# ATX_PSU_rev0_1.net
KiCad netlist of a schematic drawn in EAGLE
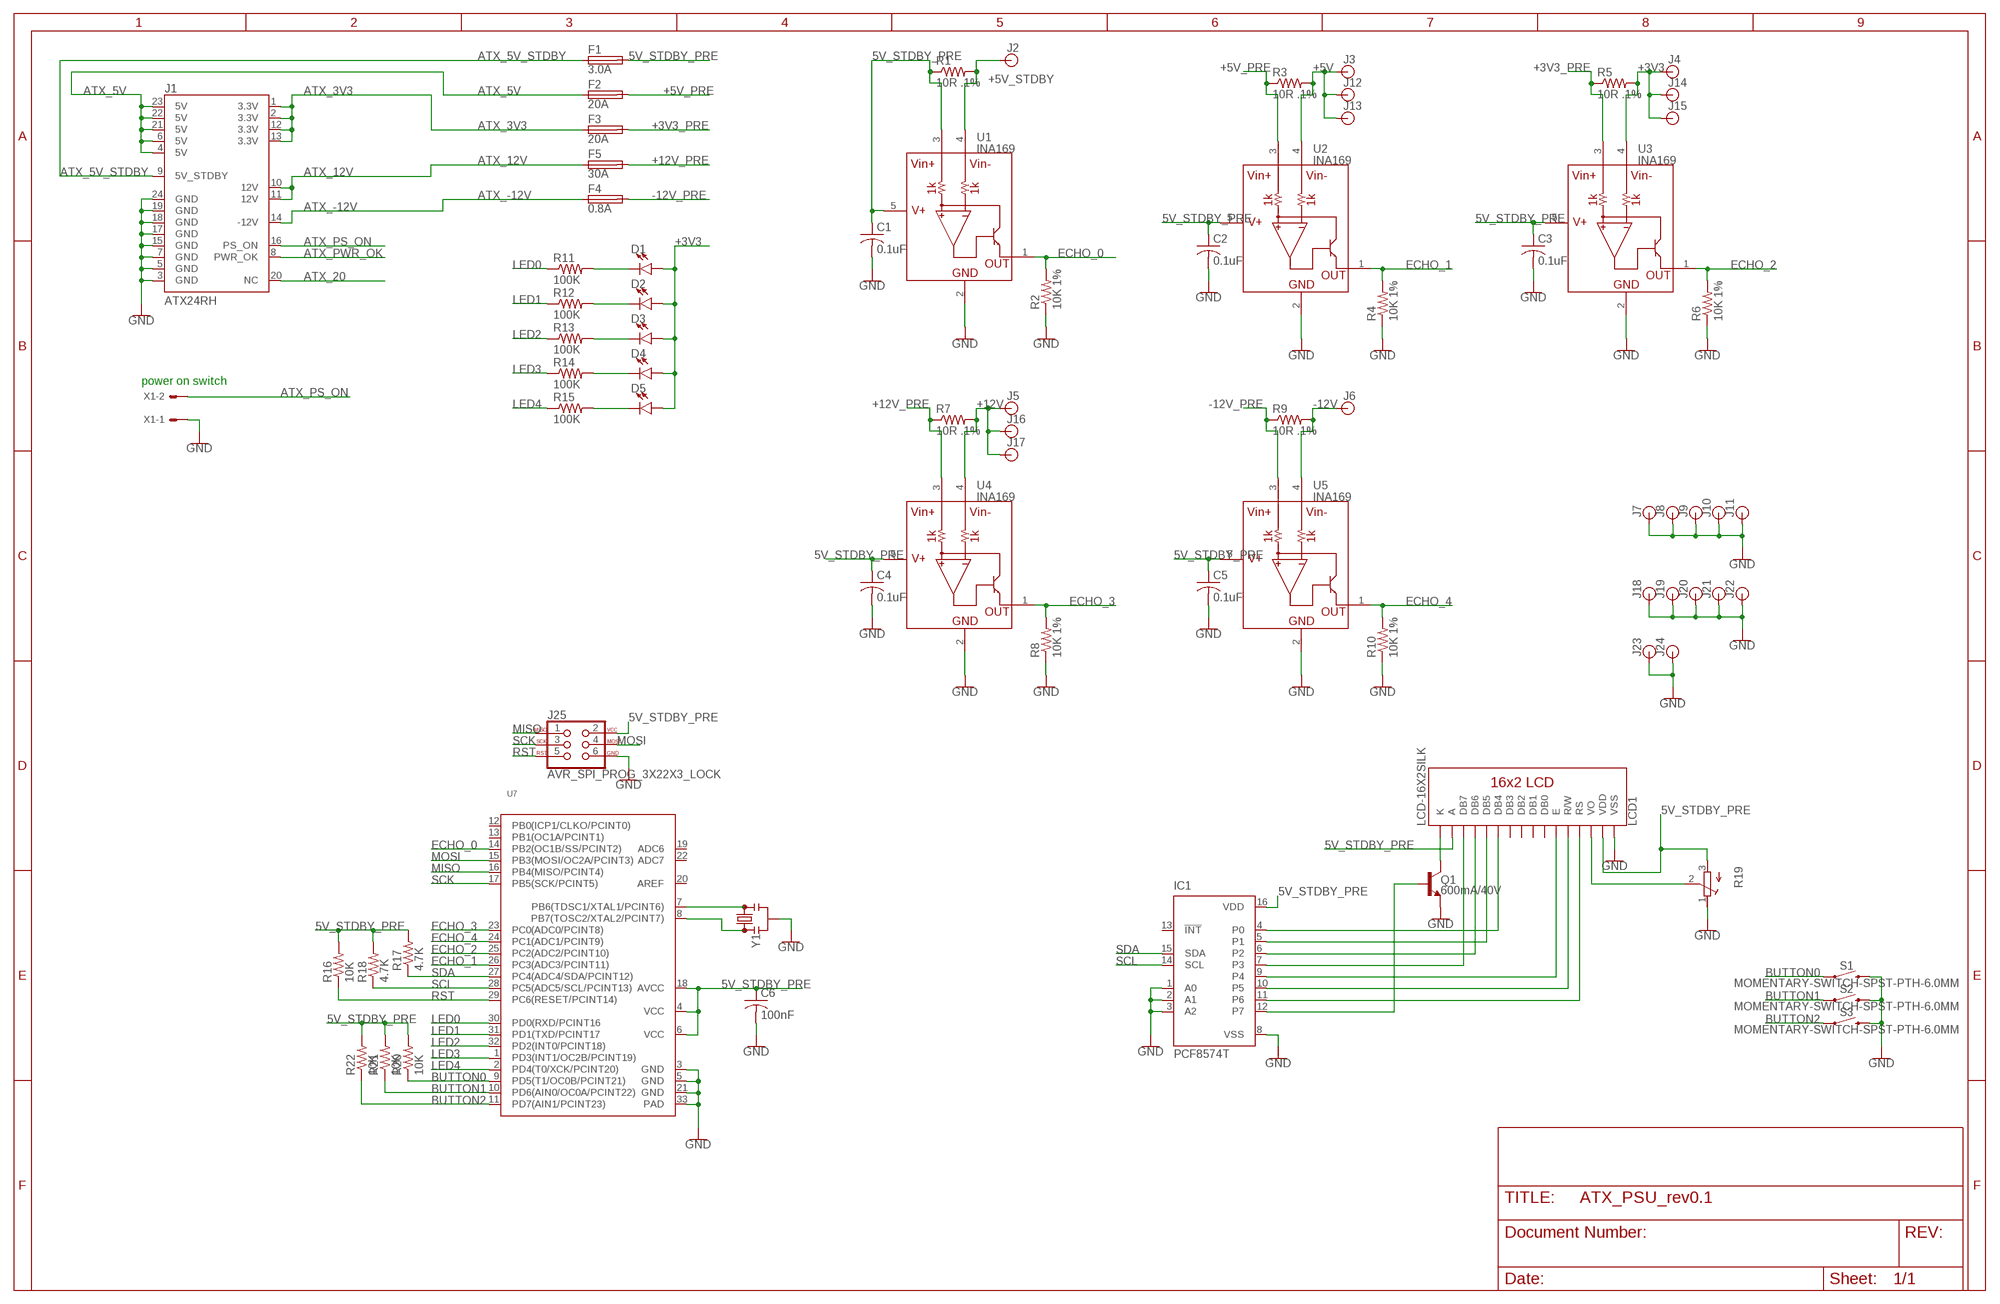
[diagram p0: schematic, sheet 1]

(export (version "E")
  (design (tool "Eeschema 10.0.6"))
  (components
    (comp (ref "C1")
      (value "0.1uF")
      (footprint "eagle-import:C1206")
      (libsource (lib "eagle-import") (part "C-USC1206"))
    )
    (comp (ref "C2")
      (value "0.1uF")
      (footprint "eagle-import:C1206")
      (libsource (lib "eagle-import") (part "C-USC1206"))
    )
    (comp (ref "C3")
      (value "0.1uF")
      (footprint "eagle-import:C1206")
      (libsource (lib "eagle-import") (part "C-USC1206"))
    )
    (comp (ref "C4")
      (value "0.1uF")
      (footprint "eagle-import:C1206")
      (libsource (lib "eagle-import") (part "C-USC1206"))
    )
    (comp (ref "C5")
      (value "0.1uF")
      (footprint "eagle-import:C1206")
      (libsource (lib "eagle-import") (part "C-USC1206"))
    )
    (comp (ref "C6")
      (value "100nF")
      (footprint "eagle-import:C1206")
      (libsource (lib "eagle-import") (part "C-USC1206"))
    )
    (comp (ref "D1")
      (value "LED-FKIT-1206")
      (footprint "eagle-import:FKIT-LED-1206")
      (libsource (lib "eagle-import") (part "LED-FKIT-1206"))
    )
    (comp (ref "D2")
      (value "LED-FKIT-1206")
      (footprint "eagle-import:FKIT-LED-1206")
      (libsource (lib "eagle-import") (part "LED-FKIT-1206"))
    )
    (comp (ref "D3")
      (value "LED-FKIT-1206")
      (footprint "eagle-import:FKIT-LED-1206")
      (libsource (lib "eagle-import") (part "LED-FKIT-1206"))
    )
    (comp (ref "D4")
      (value "LED-FKIT-1206")
      (footprint "eagle-import:FKIT-LED-1206")
      (libsource (lib "eagle-import") (part "LED-FKIT-1206"))
    )
    (comp (ref "D5")
      (value "LED-FKIT-1206")
      (footprint "eagle-import:FKIT-LED-1206")
      (libsource (lib "eagle-import") (part "LED-FKIT-1206"))
    )
    (comp (ref "F1")
      (value "3.0A")
      (footprint "eagle-import:FUSE_HOLDER_5X20MM")
      (libsource (lib "eagle-import") (part "FUSEBLANK_5X20MM"))
    )
    (comp (ref "F2")
      (value "20A")
      (footprint "eagle-import:FUSE_HOLDER_5X20MM")
      (libsource (lib "eagle-import") (part "FUSEBLANK_5X20MM"))
    )
    (comp (ref "F3")
      (value "20A")
      (footprint "eagle-import:FUSE_HOLDER_5X20MM")
      (libsource (lib "eagle-import") (part "FUSEBLANK_5X20MM"))
    )
    (comp (ref "F4")
      (value "0.8A")
      (footprint "eagle-import:FUSE_HOLDER_5X20MM")
      (libsource (lib "eagle-import") (part "FUSEBLANK_5X20MM"))
    )
    (comp (ref "F5")
      (value "30A")
      (footprint "eagle-import:FUSE_HOLDER_5X20MM")
      (libsource (lib "eagle-import") (part "FUSEBLANK_5X20MM"))
    )
    (comp (ref "IC1")
      (value "PCF8574T")
      (footprint "eagle-import:SO16W")
      (fields (field (name "MPN") "PCF8574T/3,512"))
      (libsource (lib "eagle-import") (part "PCF8574T"))
    )
    (comp (ref "J1")
      (value "ATX24RH")
      (footprint "eagle-import:ATX24_RIGHT_ANGLE")
      (libsource (lib "eagle-import") (part "ATX24RH"))
    )
    (comp (ref "J2")
      (value "BANANA_CONN")
      (footprint "eagle-import:BANANA_CONN")
      (libsource (lib "eagle-import") (part "BANANA_CONN"))
    )
    (comp (ref "J3")
      (value "BANANA_CONN")
      (footprint "eagle-import:BANANA_CONN")
      (libsource (lib "eagle-import") (part "BANANA_CONN"))
    )
    (comp (ref "J4")
      (value "BANANA_CONN")
      (footprint "eagle-import:BANANA_CONN")
      (libsource (lib "eagle-import") (part "BANANA_CONN"))
    )
    (comp (ref "J5")
      (value "BANANA_CONN")
      (footprint "eagle-import:BANANA_CONN")
      (libsource (lib "eagle-import") (part "BANANA_CONN"))
    )
    (comp (ref "J6")
      (value "BANANA_CONN")
      (footprint "eagle-import:BANANA_CONN")
      (libsource (lib "eagle-import") (part "BANANA_CONN"))
    )
    (comp (ref "J7")
      (value "BANANA_CONN")
      (footprint "eagle-import:BANANA_CONN")
      (libsource (lib "eagle-import") (part "BANANA_CONN"))
    )
    (comp (ref "J8")
      (value "BANANA_CONN")
      (footprint "eagle-import:BANANA_CONN")
      (libsource (lib "eagle-import") (part "BANANA_CONN"))
    )
    (comp (ref "J9")
      (value "BANANA_CONN")
      (footprint "eagle-import:BANANA_CONN")
      (libsource (lib "eagle-import") (part "BANANA_CONN"))
    )
    (comp (ref "J10")
      (value "BANANA_CONN")
      (footprint "eagle-import:BANANA_CONN")
      (libsource (lib "eagle-import") (part "BANANA_CONN"))
    )
    (comp (ref "J11")
      (value "BANANA_CONN")
      (footprint "eagle-import:BANANA_CONN")
      (libsource (lib "eagle-import") (part "BANANA_CONN"))
    )
    (comp (ref "J12")
      (value "BANANA_CONN")
      (footprint "eagle-import:BANANA_CONN")
      (libsource (lib "eagle-import") (part "BANANA_CONN"))
    )
    (comp (ref "J13")
      (value "BANANA_CONN")
      (footprint "eagle-import:BANANA_CONN")
      (libsource (lib "eagle-import") (part "BANANA_CONN"))
    )
    (comp (ref "J14")
      (value "BANANA_CONN")
      (footprint "eagle-import:BANANA_CONN")
      (libsource (lib "eagle-import") (part "BANANA_CONN"))
    )
    (comp (ref "J15")
      (value "BANANA_CONN")
      (footprint "eagle-import:BANANA_CONN")
      (libsource (lib "eagle-import") (part "BANANA_CONN"))
    )
    (comp (ref "J16")
      (value "BANANA_CONN")
      (footprint "eagle-import:BANANA_CONN")
      (libsource (lib "eagle-import") (part "BANANA_CONN"))
    )
    (comp (ref "J17")
      (value "BANANA_CONN")
      (footprint "eagle-import:BANANA_CONN")
      (libsource (lib "eagle-import") (part "BANANA_CONN"))
    )
    (comp (ref "J18")
      (value "BANANA_CONN")
      (footprint "eagle-import:BANANA_CONN")
      (libsource (lib "eagle-import") (part "BANANA_CONN"))
    )
    (comp (ref "J19")
      (value "BANANA_CONN")
      (footprint "eagle-import:BANANA_CONN")
      (libsource (lib "eagle-import") (part "BANANA_CONN"))
    )
    (comp (ref "J20")
      (value "BANANA_CONN")
      (footprint "eagle-import:BANANA_CONN")
      (libsource (lib "eagle-import") (part "BANANA_CONN"))
    )
    (comp (ref "J21")
      (value "BANANA_CONN")
      (footprint "eagle-import:BANANA_CONN")
      (libsource (lib "eagle-import") (part "BANANA_CONN"))
    )
    (comp (ref "J22")
      (value "BANANA_CONN")
      (footprint "eagle-import:BANANA_CONN")
      (libsource (lib "eagle-import") (part "BANANA_CONN"))
    )
    (comp (ref "J23")
      (value "BANANA_CONN")
      (footprint "eagle-import:BANANA_CONN")
      (libsource (lib "eagle-import") (part "BANANA_CONN"))
    )
    (comp (ref "J24")
      (value "BANANA_CONN")
      (footprint "eagle-import:BANANA_CONN")
      (libsource (lib "eagle-import") (part "BANANA_CONN"))
    )
    (comp (ref "J25")
      (value "AVR_SPI_PROG_3X22X3_LOCK")
      (footprint "eagle-import:2X3_LOCK")
      (libsource (lib "eagle-import") (part "AVR_SPI_PROG_3X22X3_LOCK"))
    )
    (comp (ref "LCD1")
      (value "LCD-16X2SILK")
      (footprint "eagle-import:LCD-16X2")
      (libsource (lib "eagle-import") (part "LCD-16X2SILK"))
    )
    (comp (ref "Q1")
      (value "600mA/40V")
      (footprint "eagle-import:SOT23-3")
      (libsource (lib "eagle-import") (part "TRANS_NPN-MMBT2222AL"))
    )
    (comp (ref "R1")
      (value "10R .1%")
      (footprint "eagle-import:R1206")
      (libsource (lib "eagle-import") (part "R-US_R1206"))
    )
    (comp (ref "R2")
      (value "10K 1%")
      (footprint "eagle-import:R1206")
      (libsource (lib "eagle-import") (part "R-US_R1206"))
    )
    (comp (ref "R3")
      (value "10R .1%")
      (footprint "eagle-import:R1206")
      (libsource (lib "eagle-import") (part "R-US_R1206"))
    )
    (comp (ref "R4")
      (value "10K 1%")
      (footprint "eagle-import:R1206")
      (libsource (lib "eagle-import") (part "R-US_R1206"))
    )
    (comp (ref "R5")
      (value "10R .1%")
      (footprint "eagle-import:R1206")
      (libsource (lib "eagle-import") (part "R-US_R1206"))
    )
    (comp (ref "R6")
      (value "10K 1%")
      (footprint "eagle-import:R1206")
      (libsource (lib "eagle-import") (part "R-US_R1206"))
    )
    (comp (ref "R7")
      (value "10R .1%")
      (footprint "eagle-import:R1206")
      (libsource (lib "eagle-import") (part "R-US_R1206"))
    )
    (comp (ref "R8")
      (value "10K 1%")
      (footprint "eagle-import:R1206")
      (libsource (lib "eagle-import") (part "R-US_R1206"))
    )
    (comp (ref "R9")
      (value "10R .1%")
      (footprint "eagle-import:R1206")
      (libsource (lib "eagle-import") (part "R-US_R1206"))
    )
    (comp (ref "R10")
      (value "10K 1%")
      (footprint "eagle-import:R1206")
      (libsource (lib "eagle-import") (part "R-US_R1206"))
    )
    (comp (ref "R11")
      (value "100K")
      (footprint "eagle-import:R1206")
      (libsource (lib "eagle-import") (part "R-US_R1206"))
    )
    (comp (ref "R12")
      (value "100K")
      (footprint "eagle-import:R1206")
      (libsource (lib "eagle-import") (part "R-US_R1206"))
    )
    (comp (ref "R13")
      (value "100K")
      (footprint "eagle-import:R1206")
      (libsource (lib "eagle-import") (part "R-US_R1206"))
    )
    (comp (ref "R14")
      (value "100K")
      (footprint "eagle-import:R1206")
      (libsource (lib "eagle-import") (part "R-US_R1206"))
    )
    (comp (ref "R15")
      (value "100K")
      (footprint "eagle-import:R1206")
      (libsource (lib "eagle-import") (part "R-US_R1206"))
    )
    (comp (ref "R16")
      (value "10K")
      (footprint "eagle-import:R1206")
      (libsource (lib "eagle-import") (part "R-US_R1206"))
    )
    (comp (ref "R17")
      (value "4.7K")
      (footprint "eagle-import:R1206")
      (libsource (lib "eagle-import") (part "R-US_R1206"))
    )
    (comp (ref "R18")
      (value "4.7K")
      (footprint "eagle-import:R1206")
      (libsource (lib "eagle-import") (part "R-US_R1206"))
    )
    (comp (ref "R19")
      (value "R-TRIMM3314G")
      (footprint "eagle-import:RTRIM3314G")
      (libsource (lib "eagle-import") (part "R-TRIMM3314G"))
    )
    (comp (ref "R20")
      (value "10K")
      (footprint "eagle-import:R1206")
      (libsource (lib "eagle-import") (part "R-US_R1206"))
    )
    (comp (ref "R21")
      (value "10K")
      (footprint "eagle-import:R1206")
      (libsource (lib "eagle-import") (part "R-US_R1206"))
    )
    (comp (ref "R22")
      (value "10K")
      (footprint "eagle-import:R1206")
      (libsource (lib "eagle-import") (part "R-US_R1206"))
    )
    (comp (ref "S1")
      (value "MOMENTARY-SWITCH-SPST-PTH-6.0MM")
      (footprint "eagle-import:TACTILE_SWITCH_PTH_6.0MM")
      (libsource (lib "eagle-import") (part "MOMENTARY-SWITCH-SPST-PTH-6.0MM"))
    )
    (comp (ref "S2")
      (value "MOMENTARY-SWITCH-SPST-PTH-6.0MM")
      (footprint "eagle-import:TACTILE_SWITCH_PTH_6.0MM")
      (libsource (lib "eagle-import") (part "MOMENTARY-SWITCH-SPST-PTH-6.0MM"))
    )
    (comp (ref "S3")
      (value "MOMENTARY-SWITCH-SPST-PTH-6.0MM")
      (footprint "eagle-import:TACTILE_SWITCH_PTH_6.0MM")
      (libsource (lib "eagle-import") (part "MOMENTARY-SWITCH-SPST-PTH-6.0MM"))
    )
    (comp (ref "U1")
      (value "INA169")
      (footprint "eagle-import:SOT23-5")
      (libsource (lib "eagle-import") (part "INA169"))
    )
    (comp (ref "U2")
      (value "INA169")
      (footprint "eagle-import:SOT23-5")
      (libsource (lib "eagle-import") (part "INA169"))
    )
    (comp (ref "U3")
      (value "INA169")
      (footprint "eagle-import:SOT23-5")
      (libsource (lib "eagle-import") (part "INA169"))
    )
    (comp (ref "U4")
      (value "INA169")
      (footprint "eagle-import:SOT23-5")
      (libsource (lib "eagle-import") (part "INA169"))
    )
    (comp (ref "U5")
      (value "INA169")
      (footprint "eagle-import:SOT23-5")
      (libsource (lib "eagle-import") (part "INA169"))
    )
    (comp (ref "U7")
      (value "MCU-ATMEGA168PA-MU(QFN32)")
      (footprint "eagle-import:QFN32G-0.5-5X5MM")
      (libsource (lib "eagle-import") (part "MCU-ATMEGA168PA-MU(QFN32)"))
    )
    (comp (ref "X1")
      (value "KK-156-2")
      (footprint "eagle-import:KK-156-2")
      (fields (field (name "MF") "MOLEX"))
      (libsource (lib "eagle-import") (part "KK-156-2"))
    )
    (comp (ref "Y1")
      (value "RESONATORSMD-3.2X1.3")
      (footprint "eagle-import:RESONATOR-SMD-3.2X1.3")
      (libsource (lib "eagle-import") (part "RESONATORSMD-3.2X1.3"))
    )
  )
  (nets
    (net (code "1") (name "/+3V3") (class "Default")
      (node (ref "D1") (pin "A") (pinfunction "A_A") (pintype "passive"))
      (node (ref "D2") (pin "A") (pinfunction "A_A") (pintype "passive"))
      (node (ref "D3") (pin "A") (pinfunction "A_A") (pintype "passive"))
      (node (ref "D4") (pin "A") (pinfunction "A_A") (pintype "passive"))
      (node (ref "D5") (pin "A") (pinfunction "A_A") (pintype "passive"))
      (node (ref "J14") (pin "P$1") (pinfunction "1_P$1") (pintype "passive"))
      (node (ref "J15") (pin "P$1") (pinfunction "1_P$1") (pintype "passive"))
      (node (ref "J4") (pin "P$1") (pinfunction "1_P$1") (pintype "passive"))
      (node (ref "R5") (pin "2") (pinfunction "2_2") (pintype "passive"))
      (node (ref "U3") (pin "4") (pinfunction "VIN-_4") (pintype "bidirectional"))
    )
    (net (code "2") (name "/+3V3_PRE") (class "Default")
      (node (ref "F3") (pin "2") (pinfunction "2_2") (pintype "passive"))
      (node (ref "R5") (pin "1") (pinfunction "1_1") (pintype "passive"))
      (node (ref "U3") (pin "3") (pinfunction "VIN+_3") (pintype "bidirectional"))
    )
    (net (code "3") (name "/+5V") (class "Default")
      (node (ref "J12") (pin "P$1") (pinfunction "1_P$1") (pintype "passive"))
      (node (ref "J13") (pin "P$1") (pinfunction "1_P$1") (pintype "passive"))
      (node (ref "J3") (pin "P$1") (pinfunction "1_P$1") (pintype "passive"))
      (node (ref "R3") (pin "2") (pinfunction "2_2") (pintype "passive"))
      (node (ref "U2") (pin "4") (pinfunction "VIN-_4") (pintype "bidirectional"))
    )
    (net (code "4") (name "/+5V_PRE") (class "Default")
      (node (ref "F2") (pin "2") (pinfunction "2_2") (pintype "passive"))
      (node (ref "R3") (pin "1") (pinfunction "1_1") (pintype "passive"))
      (node (ref "U2") (pin "3") (pinfunction "VIN+_3") (pintype "bidirectional"))
    )
    (net (code "5") (name "/+5V_STDBY") (class "Default")
      (node (ref "J2") (pin "P$1") (pinfunction "1_P$1") (pintype "passive"))
      (node (ref "R1") (pin "2") (pinfunction "2_2") (pintype "passive"))
      (node (ref "U1") (pin "4") (pinfunction "VIN-_4") (pintype "bidirectional"))
    )
    (net (code "6") (name "/+12V") (class "Default")
      (node (ref "J16") (pin "P$1") (pinfunction "1_P$1") (pintype "passive"))
      (node (ref "J17") (pin "P$1") (pinfunction "1_P$1") (pintype "passive"))
      (node (ref "J5") (pin "P$1") (pinfunction "1_P$1") (pintype "passive"))
      (node (ref "R7") (pin "2") (pinfunction "2_2") (pintype "passive"))
      (node (ref "U4") (pin "4") (pinfunction "VIN-_4") (pintype "bidirectional"))
    )
    (net (code "7") (name "/+12V_PRE") (class "Default")
      (node (ref "F5") (pin "2") (pinfunction "2_2") (pintype "passive"))
      (node (ref "R7") (pin "1") (pinfunction "1_1") (pintype "passive"))
      (node (ref "U4") (pin "3") (pinfunction "VIN+_3") (pintype "bidirectional"))
    )
    (net (code "8") (name "/-12V") (class "Default")
      (node (ref "J6") (pin "P$1") (pinfunction "1_P$1") (pintype "passive"))
      (node (ref "R9") (pin "2") (pinfunction "2_2") (pintype "passive"))
      (node (ref "U5") (pin "4") (pinfunction "VIN-_4") (pintype "bidirectional"))
    )
    (net (code "9") (name "/-12V_PRE") (class "Default")
      (node (ref "F4") (pin "2") (pinfunction "2_2") (pintype "passive"))
      (node (ref "R9") (pin "1") (pinfunction "1_1") (pintype "passive"))
      (node (ref "U5") (pin "3") (pinfunction "VIN+_3") (pintype "bidirectional"))
    )
    (net (code "10") (name "/5V_STDBY_PRE") (class "Default")
      (node (ref "C1") (pin "1") (pinfunction "1_1") (pintype "passive"))
      (node (ref "C2") (pin "1") (pinfunction "1_1") (pintype "passive"))
      (node (ref "C3") (pin "1") (pinfunction "1_1") (pintype "passive"))
      (node (ref "C4") (pin "1") (pinfunction "1_1") (pintype "passive"))
      (node (ref "C5") (pin "1") (pinfunction "1_1") (pintype "passive"))
      (node (ref "C6") (pin "1") (pinfunction "1_1") (pintype "passive"))
      (node (ref "F1") (pin "2") (pinfunction "2_2") (pintype "passive"))
      (node (ref "IC1") (pin "16") (pinfunction "VDD_16") (pintype "power_in"))
      (node (ref "J25") (pin "2") (pinfunction "2_2") (pintype "passive"))
      (node (ref "LCD1") (pin "15") (pinfunction "A_15") (pintype "power_in"))
      (node (ref "LCD1") (pin "2") (pinfunction "VDD_2") (pintype "power_in"))
      (node (ref "R1") (pin "1") (pinfunction "1_1") (pintype "passive"))
      (node (ref "R16") (pin "2") (pinfunction "2_2") (pintype "passive"))
      (node (ref "R17") (pin "2") (pinfunction "2_2") (pintype "passive"))
      (node (ref "R18") (pin "2") (pinfunction "2_2") (pintype "passive"))
      (node (ref "R19") (pin "3") (pinfunction "A_3") (pintype "passive"))
      (node (ref "R20") (pin "2") (pinfunction "2_2") (pintype "passive"))
      (node (ref "R21") (pin "2") (pinfunction "2_2") (pintype "passive"))
      (node (ref "R22") (pin "2") (pinfunction "2_2") (pintype "passive"))
      (node (ref "U1") (pin "3") (pinfunction "VIN+_3") (pintype "bidirectional"))
      (node (ref "U1") (pin "5") (pinfunction "V+_5") (pintype "bidirectional"))
      (node (ref "U2") (pin "5") (pinfunction "V+_5") (pintype "bidirectional"))
      (node (ref "U3") (pin "5") (pinfunction "V+_5") (pintype "bidirectional"))
      (node (ref "U4") (pin "5") (pinfunction "V+_5") (pintype "bidirectional"))
      (node (ref "U5") (pin "5") (pinfunction "V+_5") (pintype "bidirectional"))
      (node (ref "U7") (pin "18") (pinfunction "AVCC_18") (pintype "bidirectional"))
      (node (ref "U7") (pin "4") (pinfunction "VCC_4") (pintype "bidirectional"))
      (node (ref "U7") (pin "6") (pinfunction "VCC_6") (pintype "bidirectional"))
    )
    (net (code "11") (name "/ATX_-12V") (class "Default")
      (node (ref "F4") (pin "1") (pinfunction "1_1") (pintype "passive"))
      (node (ref "J1") (pin "14") (pinfunction "-12V_14") (pintype "bidirectional"))
    )
    (net (code "12") (name "/ATX_3V3") (class "Default")
      (node (ref "F3") (pin "1") (pinfunction "1_1") (pintype "passive"))
      (node (ref "J1") (pin "1") (pinfunction "3.3V_1") (pintype "bidirectional"))
      (node (ref "J1") (pin "12") (pinfunction "3.3V_12") (pintype "bidirectional"))
      (node (ref "J1") (pin "13") (pinfunction "3.3V_13") (pintype "bidirectional"))
      (node (ref "J1") (pin "2") (pinfunction "3.3V_2") (pintype "bidirectional"))
    )
    (net (code "13") (name "/ATX_5V") (class "Default")
      (node (ref "F2") (pin "1") (pinfunction "1_1") (pintype "passive"))
      (node (ref "J1") (pin "21") (pinfunction "5V_21") (pintype "bidirectional"))
      (node (ref "J1") (pin "22") (pinfunction "5V_22") (pintype "bidirectional"))
      (node (ref "J1") (pin "23") (pinfunction "5V_23") (pintype "bidirectional"))
      (node (ref "J1") (pin "4") (pinfunction "5V_4") (pintype "bidirectional"))
      (node (ref "J1") (pin "6") (pinfunction "5V_6") (pintype "bidirectional"))
    )
    (net (code "14") (name "/ATX_5V_STDBY") (class "Default")
      (node (ref "F1") (pin "1") (pinfunction "1_1") (pintype "passive"))
      (node (ref "J1") (pin "9") (pinfunction "5V_STDBY_9") (pintype "bidirectional"))
    )
    (net (code "15") (name "/ATX_12V") (class "Default")
      (node (ref "F5") (pin "1") (pinfunction "1_1") (pintype "passive"))
      (node (ref "J1") (pin "10") (pinfunction "12V_10") (pintype "bidirectional"))
      (node (ref "J1") (pin "11") (pinfunction "12V_11") (pintype "bidirectional"))
    )
    (net (code "16") (name "/ATX_20") (class "Default")
      (node (ref "J1") (pin "20") (pinfunction "NC_20") (pintype "bidirectional"))
    )
    (net (code "17") (name "/ATX_PS_ON") (class "Default")
      (node (ref "J1") (pin "16") (pinfunction "PS_ON_16") (pintype "bidirectional"))
      (node (ref "X1") (pin "2") (pinfunction "S_2") (pintype "passive"))
    )
    (net (code "18") (name "/ATX_PWR_OK") (class "Default")
      (node (ref "J1") (pin "8") (pinfunction "PWR_OK_8") (pintype "bidirectional"))
    )
    (net (code "19") (name "/BUTTON0") (class "Default")
      (node (ref "R20") (pin "1") (pinfunction "1_1") (pintype "passive"))
      (node (ref "S1") (pin "1") (pinfunction "1_1") (pintype "passive"))
      (node (ref "U7") (pin "9") (pinfunction "PD5(T1/OC0B/PCINT21)_9") (pintype "bidirectional"))
    )
    (net (code "20") (name "/BUTTON1") (class "Default")
      (node (ref "R21") (pin "1") (pinfunction "1_1") (pintype "passive"))
      (node (ref "S2") (pin "1") (pinfunction "1_1") (pintype "passive"))
      (node (ref "U7") (pin "10") (pinfunction "PD6(AIN0/OC0A/PCINT22)_10") (pintype "bidirectional"))
    )
    (net (code "21") (name "/BUTTON2") (class "Default")
      (node (ref "R22") (pin "1") (pinfunction "1_1") (pintype "passive"))
      (node (ref "S3") (pin "1") (pinfunction "1_1") (pintype "passive"))
      (node (ref "U7") (pin "11") (pinfunction "PD7(AIN1/PCINT23)_11") (pintype "bidirectional"))
    )
    (net (code "22") (name "/ECHO_0") (class "Default")
      (node (ref "R2") (pin "2") (pinfunction "2_2") (pintype "passive"))
      (node (ref "U1") (pin "1") (pinfunction "OUT_1") (pintype "bidirectional"))
      (node (ref "U7") (pin "14") (pinfunction "PB2(OC1B/SS/PCINT2)_14") (pintype "bidirectional"))
    )
    (net (code "23") (name "/ECHO_1") (class "Default")
      (node (ref "R4") (pin "2") (pinfunction "2_2") (pintype "passive"))
      (node (ref "U2") (pin "1") (pinfunction "OUT_1") (pintype "bidirectional"))
      (node (ref "U7") (pin "26") (pinfunction "PC3(ADC3/PCINT11)_26") (pintype "bidirectional"))
    )
    (net (code "24") (name "/ECHO_2") (class "Default")
      (node (ref "R6") (pin "2") (pinfunction "2_2") (pintype "passive"))
      (node (ref "U3") (pin "1") (pinfunction "OUT_1") (pintype "bidirectional"))
      (node (ref "U7") (pin "25") (pinfunction "PC2(ADC2/PCINT10)_25") (pintype "bidirectional"))
    )
    (net (code "25") (name "/ECHO_3") (class "Default")
      (node (ref "R8") (pin "2") (pinfunction "2_2") (pintype "passive"))
      (node (ref "U4") (pin "1") (pinfunction "OUT_1") (pintype "bidirectional"))
      (node (ref "U7") (pin "23") (pinfunction "PC0(ADC0/PCINT8)_23") (pintype "bidirectional"))
    )
    (net (code "26") (name "/ECHO_4") (class "Default")
      (node (ref "R10") (pin "2") (pinfunction "2_2") (pintype "passive"))
      (node (ref "U5") (pin "1") (pinfunction "OUT_1") (pintype "bidirectional"))
      (node (ref "U7") (pin "24") (pinfunction "PC1(ADC1/PCINT9)_24") (pintype "bidirectional"))
    )
    (net (code "27") (name "/LED0") (class "Default")
      (node (ref "R11") (pin "1") (pinfunction "1_1") (pintype "passive"))
      (node (ref "U7") (pin "30") (pinfunction "PD0(RXD/PCINT16_30") (pintype "bidirectional"))
    )
    (net (code "28") (name "/LED1") (class "Default")
      (node (ref "R12") (pin "1") (pinfunction "1_1") (pintype "passive"))
      (node (ref "U7") (pin "31") (pinfunction "PD1(TXD/PCINT17_31") (pintype "bidirectional"))
    )
    (net (code "29") (name "/LED2") (class "Default")
      (node (ref "R13") (pin "1") (pinfunction "1_1") (pintype "passive"))
      (node (ref "U7") (pin "32") (pinfunction "PD2(INT0/PCINT18)_32") (pintype "bidirectional"))
    )
    (net (code "30") (name "/LED3") (class "Default")
      (node (ref "R14") (pin "1") (pinfunction "1_1") (pintype "passive"))
      (node (ref "U7") (pin "1") (pinfunction "PD3(INT1/OC2B/PCINT19)_1") (pintype "bidirectional"))
    )
    (net (code "31") (name "/LED4") (class "Default")
      (node (ref "R15") (pin "1") (pinfunction "1_1") (pintype "passive"))
      (node (ref "U7") (pin "2") (pinfunction "PD4(T0/XCK/PCINT20)_2") (pintype "bidirectional"))
    )
    (net (code "32") (name "/MISO") (class "Default")
      (node (ref "J25") (pin "1") (pinfunction "1_1") (pintype "passive"))
      (node (ref "U7") (pin "16") (pinfunction "PB4(MISO/PCINT4)_16") (pintype "bidirectional"))
    )
    (net (code "33") (name "/MOSI") (class "Default")
      (node (ref "J25") (pin "4") (pinfunction "4_4") (pintype "passive"))
      (node (ref "U7") (pin "15") (pinfunction "PB3(MOSI/OC2A/PCINT3)_15") (pintype "bidirectional"))
    )
    (net (code "34") (name "/RST") (class "Default")
      (node (ref "J25") (pin "5") (pinfunction "5_5") (pintype "passive"))
      (node (ref "R16") (pin "1") (pinfunction "1_1") (pintype "passive"))
      (node (ref "U7") (pin "29") (pinfunction "PC6(RESET/PCINT14)_29") (pintype "bidirectional"))
    )
    (net (code "35") (name "/SCK") (class "Default")
      (node (ref "J25") (pin "3") (pinfunction "3_3") (pintype "passive"))
      (node (ref "U7") (pin "17") (pinfunction "PB5(SCK/PCINT5)_17") (pintype "bidirectional"))
    )
    (net (code "36") (name "/SCL") (class "Default")
      (node (ref "IC1") (pin "14") (pinfunction "SCL_14") (pintype "input"))
      (node (ref "R18") (pin "1") (pinfunction "1_1") (pintype "passive"))
      (node (ref "U7") (pin "28") (pinfunction "PC5(ADC5/SCL/PCINT13)_28") (pintype "bidirectional"))
    )
    (net (code "37") (name "/SDA") (class "Default")
      (node (ref "IC1") (pin "15") (pinfunction "SDA_15") (pintype "bidirectional"))
      (node (ref "R17") (pin "1") (pinfunction "1_1") (pintype "passive"))
      (node (ref "U7") (pin "27") (pinfunction "PC4(ADC4/SDA/PCINT12)_27") (pintype "bidirectional"))
    )
    (net (code "38") (name "GND") (class "Default")
      (node (ref "C1") (pin "2") (pinfunction "2_2") (pintype "passive"))
      (node (ref "C2") (pin "2") (pinfunction "2_2") (pintype "passive"))
      (node (ref "C3") (pin "2") (pinfunction "2_2") (pintype "passive"))
      (node (ref "C4") (pin "2") (pinfunction "2_2") (pintype "passive"))
      (node (ref "C5") (pin "2") (pinfunction "2_2") (pintype "passive"))
      (node (ref "C6") (pin "2") (pinfunction "2_2") (pintype "passive"))
      (node (ref "IC1") (pin "1") (pinfunction "A0_1") (pintype "input"))
      (node (ref "IC1") (pin "2") (pinfunction "A1_2") (pintype "input"))
      (node (ref "IC1") (pin "3") (pinfunction "A2_3") (pintype "input"))
      (node (ref "IC1") (pin "8") (pinfunction "VSS_8") (pintype "power_in"))
      (node (ref "J1") (pin "15") (pinfunction "GND_15") (pintype "bidirectional"))
      (node (ref "J1") (pin "17") (pinfunction "GND_17") (pintype "bidirectional"))
      (node (ref "J1") (pin "18") (pinfunction "GND_18") (pintype "bidirectional"))
      (node (ref "J1") (pin "19") (pinfunction "GND_19") (pintype "bidirectional"))
      (node (ref "J1") (pin "24") (pinfunction "GND_24") (pintype "bidirectional"))
      (node (ref "J1") (pin "3") (pinfunction "GND_3") (pintype "bidirectional"))
      (node (ref "J1") (pin "5") (pinfunction "GND_5") (pintype "bidirectional"))
      (node (ref "J1") (pin "7") (pinfunction "GND_7") (pintype "bidirectional"))
      (node (ref "J10") (pin "P$1") (pinfunction "1_P$1") (pintype "passive"))
      (node (ref "J11") (pin "P$1") (pinfunction "1_P$1") (pintype "passive"))
      (node (ref "J18") (pin "P$1") (pinfunction "1_P$1") (pintype "passive"))
      (node (ref "J19") (pin "P$1") (pinfunction "1_P$1") (pintype "passive"))
      (node (ref "J20") (pin "P$1") (pinfunction "1_P$1") (pintype "passive"))
      (node (ref "J21") (pin "P$1") (pinfunction "1_P$1") (pintype "passive"))
      (node (ref "J22") (pin "P$1") (pinfunction "1_P$1") (pintype "passive"))
      (node (ref "J23") (pin "P$1") (pinfunction "1_P$1") (pintype "passive"))
      (node (ref "J24") (pin "P$1") (pinfunction "1_P$1") (pintype "passive"))
      (node (ref "J25") (pin "6") (pinfunction "6_6") (pintype "passive"))
      (node (ref "J7") (pin "P$1") (pinfunction "1_P$1") (pintype "passive"))
      (node (ref "J8") (pin "P$1") (pinfunction "1_P$1") (pintype "passive"))
      (node (ref "J9") (pin "P$1") (pinfunction "1_P$1") (pintype "passive"))
      (node (ref "LCD1") (pin "1") (pinfunction "VSS_1") (pintype "power_in"))
      (node (ref "Q1") (pin "2") (pinfunction "E_2") (pintype "passive"))
      (node (ref "R10") (pin "1") (pinfunction "1_1") (pintype "passive"))
      (node (ref "R19") (pin "1") (pinfunction "E_1") (pintype "passive"))
      (node (ref "R2") (pin "1") (pinfunction "1_1") (pintype "passive"))
      (node (ref "R4") (pin "1") (pinfunction "1_1") (pintype "passive"))
      (node (ref "R6") (pin "1") (pinfunction "1_1") (pintype "passive"))
      (node (ref "R8") (pin "1") (pinfunction "1_1") (pintype "passive"))
      (node (ref "S1") (pin "3") (pinfunction "2_3") (pintype "passive"))
      (node (ref "S2") (pin "3") (pinfunction "2_3") (pintype "passive"))
      (node (ref "S3") (pin "3") (pinfunction "2_3") (pintype "passive"))
      (node (ref "U1") (pin "2") (pinfunction "GND_2") (pintype "bidirectional"))
      (node (ref "U2") (pin "2") (pinfunction "GND_2") (pintype "bidirectional"))
      (node (ref "U3") (pin "2") (pinfunction "GND_2") (pintype "bidirectional"))
      (node (ref "U4") (pin "2") (pinfunction "GND_2") (pintype "bidirectional"))
      (node (ref "U5") (pin "2") (pinfunction "GND_2") (pintype "bidirectional"))
      (node (ref "U7") (pin "21") (pinfunction "GND_21") (pintype "bidirectional"))
      (node (ref "U7") (pin "3") (pinfunction "GND_3") (pintype "bidirectional"))
      (node (ref "U7") (pin "33") (pinfunction "PAD_33") (pintype "bidirectional"))
      (node (ref "U7") (pin "5") (pinfunction "GND_5") (pintype "bidirectional"))
      (node (ref "X1") (pin "1") (pinfunction "S_1") (pintype "passive"))
      (node (ref "Y1") (pin "2") (pinfunction "2_2") (pintype "passive"))
    )
    (net (code "39") (name "Net-(D1-PadC)") (class "Default")
      (node (ref "D1") (pin "C") (pinfunction "C_C") (pintype "passive"))
      (node (ref "R11") (pin "2") (pinfunction "2_2") (pintype "passive"))
    )
    (net (code "40") (name "Net-(D2-PadC)") (class "Default")
      (node (ref "D2") (pin "C") (pinfunction "C_C") (pintype "passive"))
      (node (ref "R12") (pin "2") (pinfunction "2_2") (pintype "passive"))
    )
    (net (code "41") (name "Net-(D3-PadC)") (class "Default")
      (node (ref "D3") (pin "C") (pinfunction "C_C") (pintype "passive"))
      (node (ref "R13") (pin "2") (pinfunction "2_2") (pintype "passive"))
    )
    (net (code "42") (name "Net-(D4-PadC)") (class "Default")
      (node (ref "D4") (pin "C") (pinfunction "C_C") (pintype "passive"))
      (node (ref "R14") (pin "2") (pinfunction "2_2") (pintype "passive"))
    )
    (net (code "43") (name "Net-(D5-PadC)") (class "Default")
      (node (ref "D5") (pin "C") (pinfunction "C_C") (pintype "passive"))
      (node (ref "R15") (pin "2") (pinfunction "2_2") (pintype "passive"))
    )
    (net (code "44") (name "Net-(IC1-P0)") (class "Default")
      (node (ref "IC1") (pin "4") (pinfunction "P0_4") (pintype "bidirectional"))
      (node (ref "LCD1") (pin "11") (pinfunction "DB4_11") (pintype "bidirectional"))
    )
    (net (code "45") (name "Net-(IC1-P1)") (class "Default")
      (node (ref "IC1") (pin "5") (pinfunction "P1_5") (pintype "bidirectional"))
      (node (ref "LCD1") (pin "12") (pinfunction "DB5_12") (pintype "bidirectional"))
    )
    (net (code "46") (name "Net-(IC1-P2)") (class "Default")
      (node (ref "IC1") (pin "6") (pinfunction "P2_6") (pintype "bidirectional"))
      (node (ref "LCD1") (pin "13") (pinfunction "DB6_13") (pintype "bidirectional"))
    )
    (net (code "47") (name "Net-(IC1-P3)") (class "Default")
      (node (ref "IC1") (pin "7") (pinfunction "P3_7") (pintype "bidirectional"))
      (node (ref "LCD1") (pin "14") (pinfunction "DB7_14") (pintype "bidirectional"))
    )
    (net (code "48") (name "Net-(IC1-P4)") (class "Default")
      (node (ref "IC1") (pin "9") (pinfunction "P4_9") (pintype "bidirectional"))
      (node (ref "LCD1") (pin "6") (pinfunction "E_6") (pintype "input"))
    )
    (net (code "49") (name "Net-(IC1-P5)") (class "Default")
      (node (ref "IC1") (pin "10") (pinfunction "P5_10") (pintype "bidirectional"))
      (node (ref "LCD1") (pin "5") (pinfunction "R/W_5") (pintype "input"))
    )
    (net (code "50") (name "Net-(IC1-P6)") (class "Default")
      (node (ref "IC1") (pin "11") (pinfunction "P6_11") (pintype "bidirectional"))
      (node (ref "LCD1") (pin "4") (pinfunction "RS_4") (pintype "input"))
    )
    (net (code "51") (name "Net-(IC1-P7)") (class "Default")
      (node (ref "IC1") (pin "12") (pinfunction "P7_12") (pintype "bidirectional"))
      (node (ref "Q1") (pin "1") (pinfunction "B_1") (pintype "passive"))
    )
    (net (code "52") (name "Net-(LCD1-K)") (class "Default")
      (node (ref "LCD1") (pin "16") (pinfunction "K_16") (pintype "power_in"))
      (node (ref "Q1") (pin "3") (pinfunction "C_3") (pintype "passive"))
    )
    (net (code "53") (name "Net-(LCD1-VO)") (class "Default")
      (node (ref "LCD1") (pin "3") (pinfunction "VO_3") (pintype "bidirectional"))
      (node (ref "R19") (pin "2") (pinfunction "S_2") (pintype "passive"))
    )
    (net (code "54") (name "Net-(U7-PB6(TDSC1{slash}XTAL1{slash}PCINT6))") (class "Default")
      (node (ref "U7") (pin "7") (pinfunction "PB6(TDSC1/XTAL1/PCINT6)_7") (pintype "bidirectional"))
      (node (ref "Y1") (pin "3") (pinfunction "3_3") (pintype "passive"))
    )
    (net (code "55") (name "Net-(U7-PB7(TOSC2{slash}XTAL2{slash}PCINT7))") (class "Default")
      (node (ref "U7") (pin "8") (pinfunction "PB7(TOSC2/XTAL2/PCINT7)_8") (pintype "bidirectional"))
      (node (ref "Y1") (pin "1") (pinfunction "1_1") (pintype "passive"))
    )
    (net (code "56") (name "unconnected-(IC1-~{INT}-Pad13)") (class "Default")
      (node (ref "IC1") (pin "13") (pinfunction "~{INT}_13") (pintype "output"))
    )
    (net (code "57") (name "unconnected-(LCD1-DB0-Pad7)") (class "Default")
      (node (ref "LCD1") (pin "7") (pinfunction "DB0_7") (pintype "bidirectional"))
    )
    (net (code "58") (name "unconnected-(LCD1-DB1-Pad8)") (class "Default")
      (node (ref "LCD1") (pin "8") (pinfunction "DB1_8") (pintype "bidirectional"))
    )
    (net (code "59") (name "unconnected-(LCD1-DB2-Pad9)") (class "Default")
      (node (ref "LCD1") (pin "9") (pinfunction "DB2_9") (pintype "bidirectional"))
    )
    (net (code "60") (name "unconnected-(LCD1-DB3-Pad10)") (class "Default")
      (node (ref "LCD1") (pin "10") (pinfunction "DB3_10") (pintype "bidirectional"))
    )
    (net (code "61") (name "unconnected-(U7-ADC6-Pad19)") (class "Default")
      (node (ref "U7") (pin "19") (pinfunction "ADC6_19") (pintype "bidirectional"))
    )
    (net (code "62") (name "unconnected-(U7-ADC7-Pad22)") (class "Default")
      (node (ref "U7") (pin "22") (pinfunction "ADC7_22") (pintype "bidirectional"))
    )
    (net (code "63") (name "unconnected-(U7-AREF-Pad20)") (class "Default")
      (node (ref "U7") (pin "20") (pinfunction "AREF_20") (pintype "bidirectional"))
    )
    (net (code "64") (name "unconnected-(U7-PB0(ICP1{slash}CLKO{slash}PCINT0)-Pad12)") (class "Default")
      (node (ref "U7") (pin "12") (pinfunction "PB0(ICP1/CLKO/PCINT0)_12") (pintype "bidirectional"))
    )
    (net (code "65") (name "unconnected-(U7-PB1(OC1A{slash}PCINT1)-Pad13)") (class "Default")
      (node (ref "U7") (pin "13") (pinfunction "PB1(OC1A/PCINT1)_13") (pintype "bidirectional"))
    )
  )
)
